# CH32V407VET-USB.net
KiCad netlist of a schematic drawn in Altium Designer
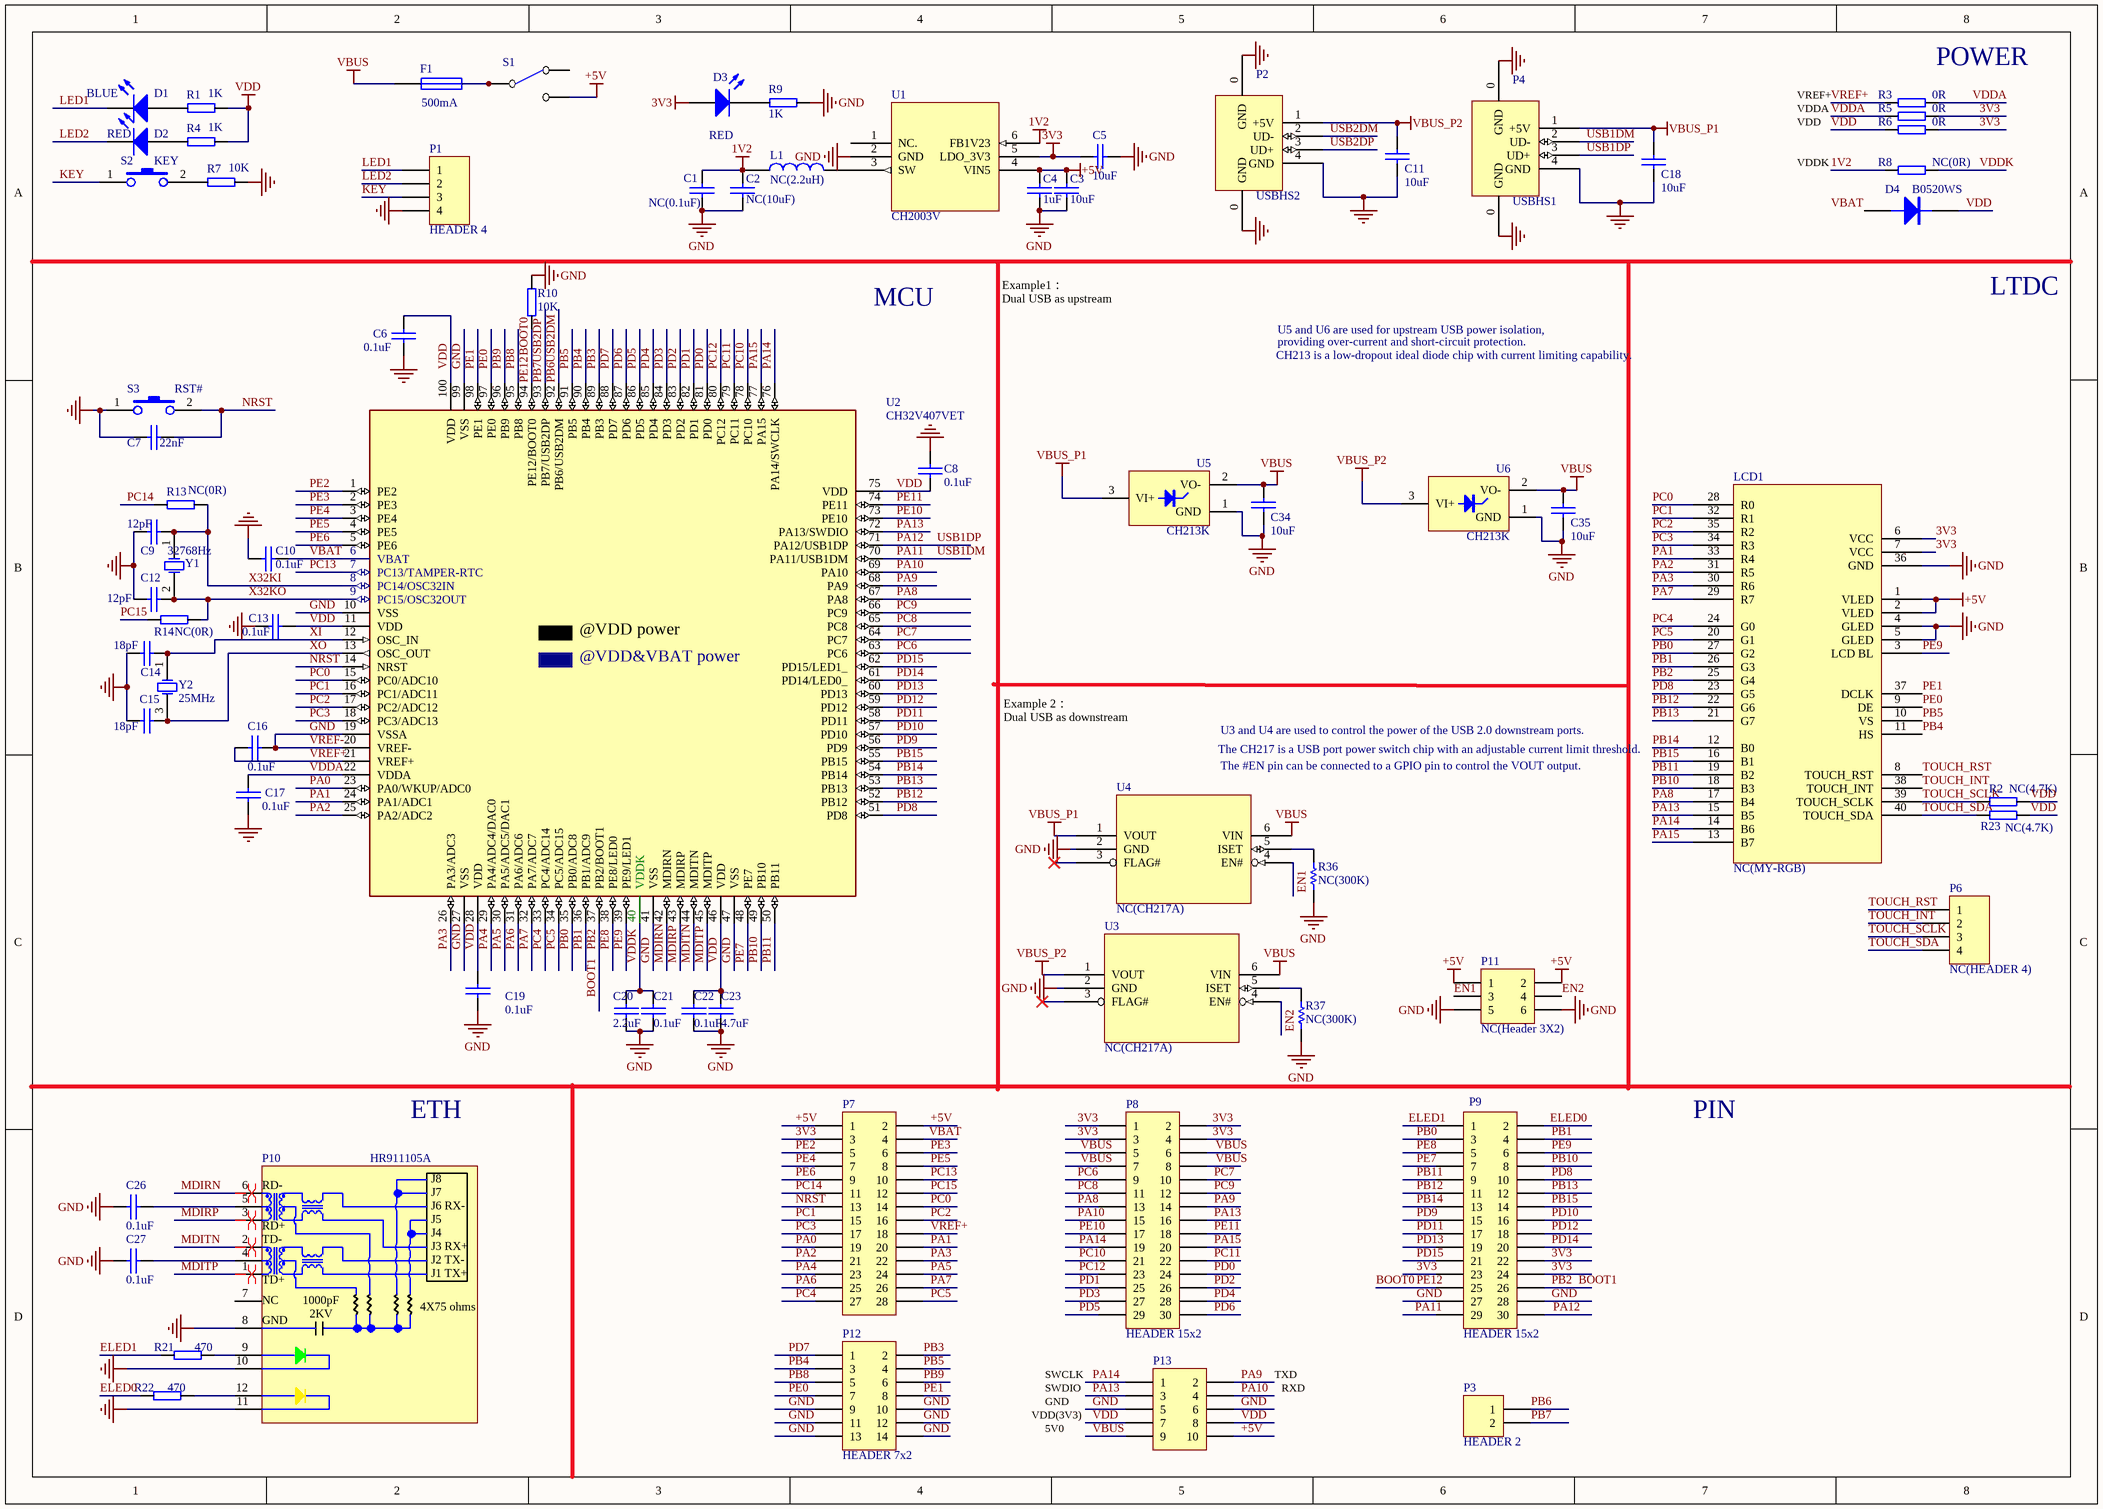
[diagram p0: CH32V407VET-USB.SchDoc]

(export (version "E")
  (design (tool "Eeschema 10.0.6"))
  (components
    (comp (ref "C1")
      (value "NC(0.1uF)")
      (footprint "0402_C")
      (description "Capacitor")
      (libsource (lib "*") (part "CAP"))
    )
    (comp (ref "C2")
      (value "NC(10uF)")
      (footprint "0603_C")
      (description "Capacitor")
      (libsource (lib "") (part "CAP_2"))
    )
    (comp (ref "C3")
      (value "10uF")
      (footprint "0603_C")
      (description "Capacitor")
      (libsource (lib "") (part "CAP_2"))
    )
    (comp (ref "C4")
      (value "1uF")
      (footprint "0402_C")
      (description "Capacitor")
      (libsource (lib "*") (part "CAP"))
    )
    (comp (ref "C5")
      (value "10uF")
      (footprint "0603_C")
      (description "Capacitor")
      (libsource (lib "") (part "CAP_2"))
    )
    (comp (ref "C6")
      (value "0.1uF")
      (footprint "0402_C")
      (description "Capacitor")
      (libsource (lib "") (part "CAP_2"))
    )
    (comp (ref "C7")
      (value "22nF")
      (footprint "0402_C")
      (description "Capacitor")
      (libsource (lib "") (part "CAP_1"))
    )
    (comp (ref "C8")
      (value "0.1uF")
      (footprint "0402_C")
      (description "Capacitor")
      (libsource (lib "") (part "CAP_2"))
    )
    (comp (ref "C9")
      (value "12pF")
      (footprint "0402_C")
      (description "Capacitor")
      (libsource (lib "") (part "CAP_2"))
    )
    (comp (ref "C10")
      (value "0.1uF")
      (footprint "0402_C")
      (description "Capacitor")
      (libsource (lib "") (part "CAP_2"))
    )
    (comp (ref "C11")
      (value "10uF")
      (footprint "0603_C")
      (description "Capacitor")
      (libsource (lib "") (part "CAP_1"))
    )
    (comp (ref "C12")
      (value "12pF")
      (footprint "0402_C")
      (description "Capacitor")
      (libsource (lib "") (part "CAP_2"))
    )
    (comp (ref "C13")
      (value "0.1uF")
      (footprint "0402_C")
      (description "Capacitor")
      (libsource (lib "") (part "CAP_2"))
    )
    (comp (ref "C14")
      (value "18pF")
      (footprint "0402_C")
      (description "Capacitor")
      (libsource (lib "") (part "CAP_2"))
    )
    (comp (ref "C15")
      (value "18pF")
      (footprint "0402_C")
      (description "Capacitor")
      (libsource (lib "") (part "CAP_2"))
    )
    (comp (ref "C16")
      (value "0.1uF")
      (footprint "0402_C")
      (description "Capacitor")
      (libsource (lib "") (part "CAP_2"))
    )
    (comp (ref "C17")
      (value "0.1uF")
      (footprint "0402_C")
      (description "Capacitor")
      (libsource (lib "") (part "CAP_2"))
    )
    (comp (ref "C18")
      (value "10uF")
      (footprint "0603_C")
      (description "Capacitor")
      (libsource (lib "") (part "CAP_1"))
    )
    (comp (ref "C19")
      (value "0.1uF")
      (footprint "0402_C")
      (description "Capacitor")
      (libsource (lib "") (part "CAP_2"))
    )
    (comp (ref "C20")
      (value "2.2uF")
      (footprint "0402_C")
      (description "Capacitor")
      (libsource (lib "") (part "CAP_2"))
    )
    (comp (ref "C21")
      (value "0.1uF")
      (footprint "0402_C")
      (description "Capacitor")
      (libsource (lib "") (part "CAP_2"))
    )
    (comp (ref "C22")
      (value "0.1uF")
      (footprint "0402_C")
      (description "Capacitor")
      (libsource (lib "") (part "CAP_2"))
    )
    (comp (ref "C23")
      (value "4.7uF")
      (footprint "0402_C")
      (description "Capacitor")
      (libsource (lib "") (part "CAP_2"))
    )
    (comp (ref "C26")
      (value "0.1uF")
      (footprint "0402_C")
      (description "Capacitor")
      (libsource (lib "wch_sch_others") (part "CAP"))
    )
    (comp (ref "C27")
      (value "0.1uF")
      (footprint "0402_C")
      (description "Capacitor")
      (libsource (lib "wch_sch_others") (part "CAP"))
    )
    (comp (ref "C34")
      (value "10uF")
      (footprint "0603_C")
      (description "Capacitor")
      (libsource (lib "") (part "CAP_1"))
    )
    (comp (ref "C35")
      (value "10uF")
      (footprint "0603_C")
      (description "Capacitor")
      (libsource (lib "") (part "CAP_1"))
    )
    (comp (ref "D1")
      (value "BLUE")
      (footprint "0603+")
      (description "Typical INFRARED GaAs LED")
      (fields (field (name "PUBLISHER") "Altium Limited"))
      (libsource (lib "*") (part "LED0"))
    )
    (comp (ref "D2")
      (value "RED")
      (footprint "0603+")
      (description "Typical INFRARED GaAs LED")
      (fields (field (name "PUBLISHER") "Altium Limited"))
      (libsource (lib "*") (part "LED0"))
    )
    (comp (ref "D3")
      (value "RED")
      (footprint "0603+")
      (description "Typical INFRARED GaAs LED")
      (fields (field (name "PUBLISHER") "Altium Limited"))
      (libsource (lib "*") (part "LED0"))
    )
    (comp (ref "D4")
      (value "B0520WS")
      (footprint "SOD-323")
      (description "Diode")
      (libsource (lib "*") (part "DIODE"))
    )
    (comp (ref "F1")
      (value "500mA")
      (footprint "0603")
      (description "Fuse")
      (libsource (lib "wch_sch_others") (part "FUSE1"))
    )
    (comp (ref "L1") (value "NC(2.2uH)") (footprint "CD32") (libsource (lib "*") (part "INDUCTOR")))
    (comp (ref "LCD1")
      (value "NC(MY-RGB)")
      (footprint "FPC40P-0.5-FK750M3")
      (libsource (lib "MY-显示") (part "MY-RGB"))
    )
    (comp (ref "P1")
      (value "HEADER 4")
      (footprint "SIP4-2.54mm")
      (description "Header, 4-Pin")
      (libsource (lib "wch_sch_others") (part "HEADER 4"))
    )
    (comp (ref "P2")
      (value "USBHS2")
      (footprint "USBAF")
      (description "USB Port")
      (libsource (lib "*") (part "USB"))
    )
    (comp (ref "P3")
      (value "HEADER 2")
      (footprint "MYPCB:SIP2-2.54mm")
      (description "Header, 2-Pin")
      (libsource (lib "wch_sch_others") (part "HEADER 2"))
    )
    (comp (ref "P4")
      (value "USBHS1")
      (footprint "USBAF")
      (description "USB Port")
      (libsource (lib "*") (part "USB"))
    )
    (comp (ref "P6")
      (value "NC(HEADER 4)")
      (footprint "SIP4-2.54mm")
      (description "Header, 4-Pin")
      (libsource (lib "wch_sch_others") (part "HEADER 4"))
    )
    (comp (ref "P7")
      (value "HEADER 14x2")
      (footprint "MYPCB:IDC28-2.54MM")
      (description "Header, 14-Pin, Dual row")
      (libsource (lib "wch_sch_others") (part "HEADER 14x2"))
    )
    (comp (ref "P8")
      (value "HEADER 15x2")
      (footprint "MYPCB:IDC30-2.54MM")
      (description "Header, 15-Pin, Dual row")
      (libsource (lib "wch_sch_others") (part "HEADER 15x2"))
    )
    (comp (ref "P9")
      (value "HEADER 15x2")
      (footprint "MYPCB:IDC30-2.54MM")
      (description "Header, 15-Pin, Dual row")
      (libsource (lib "wch_sch_others") (part "HEADER 15x2"))
    )
    (comp (ref "P10") (value "HR911105A") (footprint "HR911105A") (libsource (lib "*") (part "HR911105A")))
    (comp (ref "P11")
      (value "NC(Header 3X2)")
      (footprint "HDR2X3")
      (description "Header, 3-Pin, Dual row")
      (fields (field (name "PUBLISHER") "Altium Limited"))
      (libsource (lib "Miscellaneous Connectors") (part "Header 3X2"))
    )
    (comp (ref "P12")
      (value "HEADER 7x2")
      (footprint "MYPCB:IDC14-2.54mm")
      (description "Header, 7-Pin, Dual row")
      (libsource (lib "wch_sch_others") (part "HEADER 7x2"))
    )
    (comp (ref "P13")
      (value "LINK")
      (footprint "IDC10-2.54mm")
      (description "Header, 5-Pin, Dual row, Right Angle")
      (fields (field (name "PUBLISHER") "Altium Limited"))
      (libsource (lib "Miscellaneous Connectors") (part "Header 5X2H"))
    )
    (comp (ref "R1") (value "1K") (footprint "0402") (libsource (lib "wch_sch_others") (part "RES")))
    (comp (ref "R2") (value "NC(4.7K)") (footprint "0402") (libsource (lib "wch_sch_others") (part "RES")))
    (comp (ref "R3") (value "0R") (footprint "0402") (libsource (lib "*") (part "R")))
    (comp (ref "R4") (value "1K") (footprint "0402") (libsource (lib "wch_sch_others") (part "RES")))
    (comp (ref "R5") (value "0R") (footprint "0402") (libsource (lib "*") (part "R")))
    (comp (ref "R6") (value "0R") (footprint "0402") (libsource (lib "*") (part "R")))
    (comp (ref "R7") (value "10K") (footprint "0402") (libsource (lib "wch_sch_others") (part "RES")))
    (comp (ref "R8") (value "NC(0R)") (footprint "0402") (libsource (lib "*") (part "R")))
    (comp (ref "R9") (value "1K") (footprint "0402") (libsource (lib "wch_sch_others") (part "RES")))
    (comp (ref "R10") (value "10K") (footprint "0402") (libsource (lib "wch_sch_others") (part "RES")))
    (comp (ref "R13") (value "NC(0R)") (footprint "0402") (libsource (lib "wch_sch_others") (part "RES")))
    (comp (ref "R14") (value "NC(0R)") (footprint "0402") (libsource (lib "wch_sch_others") (part "RES")))
    (comp (ref "R21") (value "470") (footprint "0402") (libsource (lib "wch_sch_others") (part "RES")))
    (comp (ref "R22") (value "470") (footprint "0402") (libsource (lib "wch_sch_others") (part "RES")))
    (comp (ref "R23") (value "NC(4.7K)") (footprint "0402") (libsource (lib "wch_sch_others") (part "RES")))
    (comp (ref "R36")
      (value "NC(300K)")
      (footprint "0603")
      (description "Resistor")
      (fields (field (name "PUBLISHER") "Altium Limited"))
      (libsource (lib "MYLIB") (part "0603-1"))
    )
    (comp (ref "R37")
      (value "NC(300K)")
      (footprint "0603")
      (description "Resistor")
      (fields (field (name "PUBLISHER") "Altium Limited"))
      (libsource (lib "MYLIB") (part "0603-1"))
    )
    (comp (ref "S1") (value "SW SPDT") (footprint "SW1") (libsource (lib "*") (part "SW SPDT")))
    (comp (ref "S2")
      (value "KEY")
      (footprint "SMD_6.1x3.65x2.5mm-KEY")
      (libsource (lib "wch_sch_others") (part "KEY1"))
    )
    (comp (ref "S3")
      (value "RST#")
      (footprint "SMD_6.1x3.65x2.5mm-KEY")
      (libsource (lib "wch_sch_others") (part "KEY1"))
    )
    (comp (ref "U1")
      (value "CH2003V")
      (footprint "SOT-23-6")
      (description "Step-Down DC-DC Converter, 5V input, 1.23V * 800mA output, with LDO 3.3V * 200mA")
      (libsource (lib "CHXXX") (part "CH2003V"))
    )
    (comp (ref "U2")
      (value "CH32V407VET")
      (footprint "LQFP100")
      (description "RISC-V FPU HD-MCU, 175MHz, USB_480M, 100M Ethernet & Phy, CAN, DVP, ADC, DAC")
      (libsource (lib "CHXXX") (part "CH32V407VET"))
    )
    (comp (ref "U3")
      (value "NC(CH217A)")
      (footprint "SOT-23-6")
      (description "Current-Limited USB Power Distribution Switch")
      (libsource (lib "CHXXX") (part "CH217K"))
    )
    (comp (ref "U4")
      (value "NC(CH217A)")
      (footprint "SOT-23-6")
      (description "Current-Limited USB Power Distribution Switch")
      (libsource (lib "CHXXX") (part "CH217K"))
    )
    (comp (ref "U5")
      (value "CH213K")
      (footprint "SOT-23-3")
      (description "Ideal Diode 5V*1A")
      (libsource (lib "*") (part "CH213K"))
    )
    (comp (ref "U6")
      (value "CH213K")
      (footprint "SOT-23-3")
      (description "Ideal Diode 5V*1A")
      (libsource (lib "*") (part "CH213K"))
    )
    (comp (ref "Y1")
      (value "32768Hz")
      (footprint "FC-135")
      (description "Crystal Oscillator")
      (fields (field (name "PUBLISHER") "Altium Limited"))
      (libsource (lib "") (part "XTAL_1"))
    )
    (comp (ref "Y2")
      (value "25MHz")
      (footprint "XT3225")
      (description "Crystal Oscillator")
      (fields (field (name "PUBLISHER") "Altium Limited"))
      (libsource (lib "*") (part "XTAL"))
    )
  )
  (nets
    (net (code "1") (name "+5V") (class "Default")
      (node (ref "C3") (pin "2") (pinfunction "2_2") (pintype "passive"))
      (node (ref "C4") (pin "2") (pinfunction "2_2") (pintype "passive"))
      (node (ref "LCD1") (pin "1") (pinfunction "VLED_1") (pintype "passive"))
      (node (ref "LCD1") (pin "2") (pinfunction "VLED_2") (pintype "passive"))
      (node (ref "P11") (pin "1") (pinfunction "1_1") (pintype "passive"))
      (node (ref "P11") (pin "2") (pinfunction "2_2") (pintype "passive"))
      (node (ref "P13") (pin "10") (pinfunction "10_10") (pintype "passive"))
      (node (ref "P7") (pin "1") (pinfunction "1_1") (pintype "passive"))
      (node (ref "P7") (pin "2") (pinfunction "2_2") (pintype "passive"))
      (node (ref "S1") (pin "2") (pinfunction "NC_2") (pintype "passive"))
      (node (ref "U1") (pin "4") (pinfunction "VIN5_4") (pintype "power_in"))
    )
    (net (code "3") (name "/BOOT0") (class "Default")
      (node (ref "P9") (pin "25") (pinfunction "25_25") (pintype "passive"))
      (node (ref "R10") (pin "2") (pintype "passive"))
      (node (ref "U2") (pin "94") (pinfunction "PE12/BOOT0_94") (pintype "bidirectional"))
    )
    (net (code "4") (name "/BOOT1") (class "Default")
      (node (ref "LCD1") (pin "25") (pinfunction "G4_25") (pintype "passive"))
      (node (ref "P9") (pin "26") (pinfunction "26_26") (pintype "passive"))
      (node (ref "U2") (pin "37") (pinfunction "PB2/BOOT1_37") (pintype "bidirectional"))
    )
    (net (code "5") (name "/ELED0") (class "Default")
      (node (ref "P9") (pin "2") (pinfunction "2_2") (pintype "passive"))
      (node (ref "R22") (pin "1") (pintype "passive"))
    )
    (net (code "6") (name "/ELED1") (class "Default")
      (node (ref "P9") (pin "1") (pinfunction "1_1") (pintype "passive"))
      (node (ref "R21") (pin "1") (pintype "passive"))
    )
    (net (code "7") (name "/EN1") (class "Default")
      (node (ref "P11") (pin "3") (pinfunction "3_3") (pintype "passive"))
      (node (ref "U4") (pin "4") (pinfunction "EN#_4") (pintype "input"))
    )
    (net (code "8") (name "/EN2") (class "Default")
      (node (ref "P11") (pin "4") (pinfunction "4_4") (pintype "passive"))
      (node (ref "U3") (pin "4") (pinfunction "EN#_4") (pintype "input"))
    )
    (net (code "9") (name "/KEY") (class "Default")
      (node (ref "P1") (pin "3") (pinfunction "3_3") (pintype "passive"))
      (node (ref "S2") (pin "1") (pinfunction "1_1") (pintype "passive"))
    )
    (net (code "10") (name "/LED1") (class "Default")
      (node (ref "D1") (pin "2") (pinfunction "K_2") (pintype "passive"))
      (node (ref "P1") (pin "1") (pinfunction "1_1") (pintype "passive"))
    )
    (net (code "11") (name "/LED2") (class "Default")
      (node (ref "D2") (pin "2") (pinfunction "K_2") (pintype "passive"))
      (node (ref "P1") (pin "2") (pinfunction "2_2") (pintype "passive"))
    )
    (net (code "12") (name "/MDIRN") (class "Default")
      (node (ref "P10") (pin "6") (pintype "passive"))
      (node (ref "U2") (pin "42") (pinfunction "MDIRN_42") (pintype "bidirectional"))
    )
    (net (code "13") (name "/MDIRP") (class "Default")
      (node (ref "P10") (pin "3") (pintype "passive"))
      (node (ref "U2") (pin "43") (pinfunction "MDIRP_43") (pintype "bidirectional"))
    )
    (net (code "14") (name "/MDITN") (class "Default")
      (node (ref "P10") (pin "2") (pintype "passive"))
      (node (ref "U2") (pin "44") (pinfunction "MDITN_44") (pintype "bidirectional"))
    )
    (net (code "15") (name "/MDITP") (class "Default")
      (node (ref "P10") (pin "1") (pintype "passive"))
      (node (ref "U2") (pin "45") (pinfunction "MDITP_45") (pintype "bidirectional"))
    )
    (net (code "16") (name "/NRST") (class "Default")
      (node (ref "C7") (pin "2") (pinfunction "2_2") (pintype "passive"))
      (node (ref "P7") (pin "13") (pinfunction "13_13") (pintype "passive"))
      (node (ref "S3") (pin "2") (pinfunction "2_2") (pintype "passive"))
      (node (ref "U2") (pin "14") (pinfunction "NRST_14") (pintype "input"))
    )
    (net (code "17") (name "/PA0") (class "Default")
      (node (ref "P7") (pin "19") (pinfunction "19_19") (pintype "passive"))
      (node (ref "U2") (pin "23") (pinfunction "PA0/WKUP/ADC0_23") (pintype "bidirectional"))
    )
    (net (code "18") (name "/PA1") (class "Default")
      (node (ref "LCD1") (pin "33") (pinfunction "R4_33") (pintype "passive"))
      (node (ref "P7") (pin "20") (pinfunction "20_20") (pintype "passive"))
      (node (ref "U2") (pin "24") (pinfunction "PA1/ADC1_24") (pintype "bidirectional"))
    )
    (net (code "19") (name "/PA2") (class "Default")
      (node (ref "LCD1") (pin "31") (pinfunction "R5_31") (pintype "passive"))
      (node (ref "P7") (pin "21") (pinfunction "21_21") (pintype "passive"))
      (node (ref "U2") (pin "25") (pinfunction "PA2/ADC2_25") (pintype "bidirectional"))
    )
    (net (code "20") (name "/PA3") (class "Default")
      (node (ref "LCD1") (pin "30") (pinfunction "R6_30") (pintype "passive"))
      (node (ref "P7") (pin "22") (pinfunction "22_22") (pintype "passive"))
      (node (ref "U2") (pin "26") (pinfunction "PA3/ADC3_26") (pintype "bidirectional"))
    )
    (net (code "21") (name "/PA4") (class "Default")
      (node (ref "P7") (pin "23") (pinfunction "23_23") (pintype "passive"))
      (node (ref "U2") (pin "29") (pinfunction "PA4/ADC4/DAC0_29") (pintype "bidirectional"))
    )
    (net (code "22") (name "/PA5") (class "Default")
      (node (ref "P7") (pin "24") (pinfunction "24_24") (pintype "passive"))
      (node (ref "U2") (pin "30") (pinfunction "PA5/ADC5/DAC1_30") (pintype "bidirectional"))
    )
    (net (code "23") (name "/PA6") (class "Default")
      (node (ref "P7") (pin "25") (pinfunction "25_25") (pintype "passive"))
      (node (ref "U2") (pin "31") (pinfunction "PA6/ADC6_31") (pintype "bidirectional"))
    )
    (net (code "24") (name "/PA7") (class "Default")
      (node (ref "LCD1") (pin "29") (pinfunction "R7_29") (pintype "passive"))
      (node (ref "P7") (pin "26") (pinfunction "26_26") (pintype "passive"))
      (node (ref "U2") (pin "32") (pinfunction "PA7/ADC7_32") (pintype "bidirectional"))
    )
    (net (code "25") (name "/PA8") (class "Default")
      (node (ref "LCD1") (pin "17") (pinfunction "B4_17") (pintype "passive"))
      (node (ref "P8") (pin "13") (pinfunction "13_13") (pintype "passive"))
      (node (ref "U2") (pin "67") (pinfunction "PA8_67") (pintype "bidirectional"))
    )
    (net (code "26") (name "/PA9") (class "Default")
      (node (ref "P13") (pin "2") (pinfunction "2_2") (pintype "passive"))
      (node (ref "P8") (pin "14") (pinfunction "14_14") (pintype "passive"))
      (node (ref "U2") (pin "68") (pinfunction "PA9_68") (pintype "bidirectional"))
    )
    (net (code "27") (name "/PA10") (class "Default")
      (node (ref "P13") (pin "4") (pinfunction "4_4") (pintype "passive"))
      (node (ref "P8") (pin "15") (pinfunction "15_15") (pintype "passive"))
      (node (ref "U2") (pin "69") (pinfunction "PA10_69") (pintype "bidirectional"))
    )
    (net (code "28") (name "/PA11") (class "Default")
      (node (ref "P4") (pin "2") (pinfunction "UD-_2") (pintype "bidirectional"))
      (node (ref "P9") (pin "29") (pinfunction "29_29") (pintype "passive"))
      (node (ref "U2") (pin "70") (pinfunction "PA11/USB1DM_70") (pintype "bidirectional"))
    )
    (net (code "29") (name "/PA12") (class "Default")
      (node (ref "P4") (pin "3") (pinfunction "UD+_3") (pintype "bidirectional"))
      (node (ref "P9") (pin "30") (pinfunction "30_30") (pintype "passive"))
      (node (ref "U2") (pin "71") (pinfunction "PA12/USB1DP_71") (pintype "bidirectional"))
    )
    (net (code "30") (name "/PA13") (class "Default")
      (node (ref "LCD1") (pin "15") (pinfunction "B5_15") (pintype "passive"))
      (node (ref "P13") (pin "3") (pinfunction "3_3") (pintype "passive"))
      (node (ref "P8") (pin "16") (pinfunction "16_16") (pintype "passive"))
      (node (ref "U2") (pin "72") (pinfunction "PA13/SWDIO_72") (pintype "bidirectional"))
    )
    (net (code "31") (name "/PA14") (class "Default")
      (node (ref "LCD1") (pin "14") (pinfunction "B6_14") (pintype "passive"))
      (node (ref "P13") (pin "1") (pinfunction "1_1") (pintype "passive"))
      (node (ref "P8") (pin "19") (pinfunction "19_19") (pintype "passive"))
      (node (ref "U2") (pin "76") (pinfunction "PA14/SWCLK_76") (pintype "bidirectional"))
    )
    (net (code "32") (name "/PA15") (class "Default")
      (node (ref "LCD1") (pin "13") (pinfunction "B7_13") (pintype "passive"))
      (node (ref "P8") (pin "20") (pinfunction "20_20") (pintype "passive"))
      (node (ref "U2") (pin "77") (pinfunction "PA15_77") (pintype "bidirectional"))
    )
    (net (code "33") (name "/PB0") (class "Default")
      (node (ref "LCD1") (pin "27") (pinfunction "G2_27") (pintype "passive"))
      (node (ref "P9") (pin "3") (pinfunction "3_3") (pintype "passive"))
      (node (ref "U2") (pin "35") (pinfunction "PB0/ADC8_35") (pintype "bidirectional"))
    )
    (net (code "34") (name "/PB1") (class "Default")
      (node (ref "LCD1") (pin "26") (pinfunction "G3_26") (pintype "passive"))
      (node (ref "P9") (pin "4") (pinfunction "4_4") (pintype "passive"))
      (node (ref "U2") (pin "36") (pinfunction "PB1/ADC9_36") (pintype "bidirectional"))
    )
    (net (code "35") (name "/PB3") (class "Default")
      (node (ref "P12") (pin "2") (pinfunction "2_2") (pintype "passive"))
      (node (ref "U2") (pin "89") (pinfunction "PB3_89") (pintype "bidirectional"))
    )
    (net (code "36") (name "/PB4") (class "Default")
      (node (ref "LCD1") (pin "11") (pinfunction "HS_11") (pintype "passive"))
      (node (ref "P12") (pin "3") (pinfunction "3_3") (pintype "passive"))
      (node (ref "U2") (pin "90") (pinfunction "PB4_90") (pintype "bidirectional"))
    )
    (net (code "37") (name "/PB5") (class "Default")
      (node (ref "LCD1") (pin "10") (pinfunction "VS_10") (pintype "passive"))
      (node (ref "P12") (pin "4") (pinfunction "4_4") (pintype "passive"))
      (node (ref "U2") (pin "91") (pinfunction "PB5_91") (pintype "bidirectional"))
    )
    (net (code "38") (name "/PB6") (class "Default")
      (node (ref "P2") (pin "2") (pinfunction "UD-_2") (pintype "bidirectional"))
      (node (ref "P3") (pin "1") (pinfunction "1_1") (pintype "passive"))
      (node (ref "U2") (pin "92") (pinfunction "PB6/USB2DM_92") (pintype "bidirectional"))
    )
    (net (code "39") (name "/PB7") (class "Default")
      (node (ref "P2") (pin "3") (pinfunction "UD+_3") (pintype "bidirectional"))
      (node (ref "P3") (pin "2") (pinfunction "2_2") (pintype "passive"))
      (node (ref "U2") (pin "93") (pinfunction "PB7/USB2DP_93") (pintype "bidirectional"))
    )
    (net (code "40") (name "/PB8") (class "Default")
      (node (ref "P12") (pin "5") (pinfunction "5_5") (pintype "passive"))
      (node (ref "U2") (pin "95") (pinfunction "PB8_95") (pintype "bidirectional"))
    )
    (net (code "41") (name "/PB9") (class "Default")
      (node (ref "P12") (pin "6") (pinfunction "6_6") (pintype "passive"))
      (node (ref "U2") (pin "96") (pinfunction "PB9_96") (pintype "bidirectional"))
    )
    (net (code "42") (name "/PB10") (class "Default")
      (node (ref "LCD1") (pin "18") (pinfunction "B3_18") (pintype "passive"))
      (node (ref "P9") (pin "8") (pinfunction "8_8") (pintype "passive"))
      (node (ref "U2") (pin "49") (pinfunction "PB10_49") (pintype "bidirectional"))
    )
    (net (code "43") (name "/PB11") (class "Default")
      (node (ref "LCD1") (pin "19") (pinfunction "B2_19") (pintype "passive"))
      (node (ref "P9") (pin "9") (pinfunction "9_9") (pintype "passive"))
      (node (ref "U2") (pin "50") (pinfunction "PB11_50") (pintype "bidirectional"))
    )
    (net (code "44") (name "/PB12") (class "Default")
      (node (ref "LCD1") (pin "22") (pinfunction "G6_22") (pintype "passive"))
      (node (ref "P9") (pin "11") (pinfunction "11_11") (pintype "passive"))
      (node (ref "U2") (pin "52") (pinfunction "PB12_52") (pintype "bidirectional"))
    )
    (net (code "45") (name "/PB13") (class "Default")
      (node (ref "LCD1") (pin "21") (pinfunction "G7_21") (pintype "passive"))
      (node (ref "P9") (pin "12") (pinfunction "12_12") (pintype "passive"))
      (node (ref "U2") (pin "53") (pinfunction "PB13_53") (pintype "bidirectional"))
    )
    (net (code "46") (name "/PB14") (class "Default")
      (node (ref "LCD1") (pin "12") (pinfunction "B0_12") (pintype "passive"))
      (node (ref "P9") (pin "13") (pinfunction "13_13") (pintype "passive"))
      (node (ref "U2") (pin "54") (pinfunction "PB14_54") (pintype "bidirectional"))
    )
    (net (code "47") (name "/PB15") (class "Default")
      (node (ref "LCD1") (pin "16") (pinfunction "B1_16") (pintype "passive"))
      (node (ref "P9") (pin "14") (pinfunction "14_14") (pintype "passive"))
      (node (ref "U2") (pin "55") (pinfunction "PB15_55") (pintype "bidirectional"))
    )
    (net (code "48") (name "/PC0") (class "Default")
      (node (ref "LCD1") (pin "28") (pinfunction "R0_28") (pintype "passive"))
      (node (ref "P7") (pin "14") (pinfunction "14_14") (pintype "passive"))
      (node (ref "U2") (pin "15") (pinfunction "PC0/ADC10_15") (pintype "bidirectional"))
    )
    (net (code "49") (name "/PC1") (class "Default")
      (node (ref "LCD1") (pin "32") (pinfunction "R1_32") (pintype "passive"))
      (node (ref "P7") (pin "15") (pinfunction "15_15") (pintype "passive"))
      (node (ref "U2") (pin "16") (pinfunction "PC1/ADC11_16") (pintype "bidirectional"))
    )
    (net (code "50") (name "/PC2") (class "Default")
      (node (ref "LCD1") (pin "35") (pinfunction "R2_35") (pintype "passive"))
      (node (ref "P7") (pin "16") (pinfunction "16_16") (pintype "passive"))
      (node (ref "U2") (pin "17") (pinfunction "PC2/ADC12_17") (pintype "bidirectional"))
    )
    (net (code "51") (name "/PC3") (class "Default")
      (node (ref "LCD1") (pin "34") (pinfunction "R3_34") (pintype "passive"))
      (node (ref "P7") (pin "17") (pinfunction "17_17") (pintype "passive"))
      (node (ref "U2") (pin "18") (pinfunction "PC3/ADC13_18") (pintype "bidirectional"))
    )
    (net (code "52") (name "/PC4") (class "Default")
      (node (ref "LCD1") (pin "24") (pinfunction "G0_24") (pintype "passive"))
      (node (ref "P7") (pin "27") (pinfunction "27_27") (pintype "passive"))
      (node (ref "U2") (pin "33") (pinfunction "PC4/ADC14_33") (pintype "bidirectional"))
    )
    (net (code "53") (name "/PC5") (class "Default")
      (node (ref "LCD1") (pin "20") (pinfunction "G1_20") (pintype "passive"))
      (node (ref "P7") (pin "28") (pinfunction "28_28") (pintype "passive"))
      (node (ref "U2") (pin "34") (pinfunction "PC5/ADC15_34") (pintype "bidirectional"))
    )
    (net (code "54") (name "/PC6") (class "Default")
      (node (ref "P8") (pin "9") (pinfunction "9_9") (pintype "passive"))
      (node (ref "U2") (pin "63") (pinfunction "PC6_63") (pintype "bidirectional"))
    )
    (net (code "55") (name "/PC7") (class "Default")
      (node (ref "P8") (pin "10") (pinfunction "10_10") (pintype "passive"))
      (node (ref "U2") (pin "64") (pinfunction "PC7_64") (pintype "bidirectional"))
    )
    (net (code "56") (name "/PC8") (class "Default")
      (node (ref "P8") (pin "11") (pinfunction "11_11") (pintype "passive"))
      (node (ref "U2") (pin "65") (pinfunction "PC8_65") (pintype "bidirectional"))
    )
    (net (code "57") (name "/PC9") (class "Default")
      (node (ref "P8") (pin "12") (pinfunction "12_12") (pintype "passive"))
      (node (ref "U2") (pin "66") (pinfunction "PC9_66") (pintype "bidirectional"))
    )
    (net (code "58") (name "/PC10") (class "Default")
      (node (ref "P8") (pin "21") (pinfunction "21_21") (pintype "passive"))
      (node (ref "U2") (pin "78") (pinfunction "PC10_78") (pintype "bidirectional"))
    )
    (net (code "59") (name "/PC11") (class "Default")
      (node (ref "P8") (pin "22") (pinfunction "22_22") (pintype "passive"))
      (node (ref "U2") (pin "79") (pinfunction "PC11_79") (pintype "bidirectional"))
    )
    (net (code "60") (name "/PC12") (class "Default")
      (node (ref "P8") (pin "23") (pinfunction "23_23") (pintype "passive"))
      (node (ref "U2") (pin "80") (pinfunction "PC12_80") (pintype "bidirectional"))
    )
    (net (code "61") (name "/PC13") (class "Default")
      (node (ref "P7") (pin "10") (pinfunction "10_10") (pintype "passive"))
      (node (ref "U2") (pin "7") (pinfunction "PC13/TAMPER-RTC_7") (pintype "bidirectional"))
    )
    (net (code "62") (name "/PC14") (class "Default")
      (node (ref "P7") (pin "11") (pinfunction "11_11") (pintype "passive"))
      (node (ref "R13") (pin "1") (pintype "passive"))
    )
    (net (code "63") (name "/PC15") (class "Default")
      (node (ref "P7") (pin "12") (pinfunction "12_12") (pintype "passive"))
      (node (ref "R14") (pin "1") (pintype "passive"))
    )
    (net (code "64") (name "/PD0") (class "Default")
      (node (ref "P8") (pin "24") (pinfunction "24_24") (pintype "passive"))
      (node (ref "U2") (pin "81") (pinfunction "PD0_81") (pintype "bidirectional"))
    )
    (net (code "65") (name "/PD1") (class "Default")
      (node (ref "P8") (pin "25") (pinfunction "25_25") (pintype "passive"))
      (node (ref "U2") (pin "82") (pinfunction "PD1_82") (pintype "bidirectional"))
    )
    (net (code "66") (name "/PD2") (class "Default")
      (node (ref "P8") (pin "26") (pinfunction "26_26") (pintype "passive"))
      (node (ref "U2") (pin "83") (pinfunction "PD2_83") (pintype "bidirectional"))
    )
    (net (code "67") (name "/PD3") (class "Default")
      (node (ref "P8") (pin "27") (pinfunction "27_27") (pintype "passive"))
      (node (ref "U2") (pin "84") (pinfunction "PD3_84") (pintype "bidirectional"))
    )
    (net (code "68") (name "/PD4") (class "Default")
      (node (ref "P8") (pin "28") (pinfunction "28_28") (pintype "passive"))
      (node (ref "U2") (pin "85") (pinfunction "PD4_85") (pintype "bidirectional"))
    )
    (net (code "69") (name "/PD5") (class "Default")
      (node (ref "P8") (pin "29") (pinfunction "29_29") (pintype "passive"))
      (node (ref "U2") (pin "86") (pinfunction "PD5_86") (pintype "bidirectional"))
    )
    (net (code "70") (name "/PD6") (class "Default")
      (node (ref "P8") (pin "30") (pinfunction "30_30") (pintype "passive"))
      (node (ref "U2") (pin "87") (pinfunction "PD6_87") (pintype "bidirectional"))
    )
    (net (code "71") (name "/PD7") (class "Default")
      (node (ref "P12") (pin "1") (pinfunction "1_1") (pintype "passive"))
      (node (ref "U2") (pin "88") (pinfunction "PD7_88") (pintype "bidirectional"))
    )
    (net (code "72") (name "/PD8") (class "Default")
      (node (ref "LCD1") (pin "23") (pinfunction "G5_23") (pintype "passive"))
      (node (ref "P9") (pin "10") (pinfunction "10_10") (pintype "passive"))
      (node (ref "U2") (pin "51") (pinfunction "PD8_51") (pintype "bidirectional"))
    )
    (net (code "73") (name "/PD9") (class "Default")
      (node (ref "P9") (pin "15") (pinfunction "15_15") (pintype "passive"))
      (node (ref "U2") (pin "56") (pinfunction "PD9_56") (pintype "bidirectional"))
    )
    (net (code "74") (name "/PD10") (class "Default")
      (node (ref "P9") (pin "16") (pinfunction "16_16") (pintype "passive"))
      (node (ref "U2") (pin "57") (pinfunction "PD10_57") (pintype "bidirectional"))
    )
    (net (code "75") (name "/PD11") (class "Default")
      (node (ref "P9") (pin "17") (pinfunction "17_17") (pintype "passive"))
      (node (ref "U2") (pin "58") (pinfunction "PD11_58") (pintype "bidirectional"))
    )
    (net (code "76") (name "/PD12") (class "Default")
      (node (ref "P9") (pin "18") (pinfunction "18_18") (pintype "passive"))
      (node (ref "U2") (pin "59") (pinfunction "PD12_59") (pintype "bidirectional"))
    )
    (net (code "77") (name "/PD13") (class "Default")
      (node (ref "P9") (pin "19") (pinfunction "19_19") (pintype "passive"))
      (node (ref "U2") (pin "60") (pinfunction "PD13_60") (pintype "bidirectional"))
    )
    (net (code "78") (name "/PD14") (class "Default")
      (node (ref "P9") (pin "20") (pinfunction "20_20") (pintype "passive"))
      (node (ref "U2") (pin "61") (pinfunction "PD14/LED0__61") (pintype "bidirectional"))
    )
    (net (code "79") (name "/PD15") (class "Default")
      (node (ref "P9") (pin "21") (pinfunction "21_21") (pintype "passive"))
      (node (ref "U2") (pin "62") (pinfunction "PD15/LED1__62") (pintype "bidirectional"))
    )
    (net (code "80") (name "/PE0") (class "Default")
      (node (ref "LCD1") (pin "9") (pinfunction "DE_9") (pintype "passive"))
      (node (ref "P12") (pin "7") (pinfunction "7_7") (pintype "passive"))
      (node (ref "U2") (pin "97") (pinfunction "PE0_97") (pintype "bidirectional"))
    )
    (net (code "81") (name "/PE1") (class "Default")
      (node (ref "LCD1") (pin "37") (pinfunction "DCLK_37") (pintype "passive"))
      (node (ref "P12") (pin "8") (pinfunction "8_8") (pintype "passive"))
      (node (ref "U2") (pin "98") (pinfunction "PE1_98") (pintype "bidirectional"))
    )
    (net (code "82") (name "/PE2") (class "Default")
      (node (ref "P7") (pin "5") (pinfunction "5_5") (pintype "passive"))
      (node (ref "U2") (pin "1") (pinfunction "PE2_1") (pintype "bidirectional"))
    )
    (net (code "83") (name "/PE3") (class "Default")
      (node (ref "P7") (pin "6") (pinfunction "6_6") (pintype "passive"))
      (node (ref "U2") (pin "2") (pinfunction "PE3_2") (pintype "bidirectional"))
    )
    (net (code "84") (name "/PE4") (class "Default")
      (node (ref "P7") (pin "7") (pinfunction "7_7") (pintype "passive"))
      (node (ref "U2") (pin "3") (pinfunction "PE4_3") (pintype "bidirectional"))
    )
    (net (code "85") (name "/PE5") (class "Default")
      (node (ref "P7") (pin "8") (pinfunction "8_8") (pintype "passive"))
      (node (ref "U2") (pin "4") (pinfunction "PE5_4") (pintype "bidirectional"))
    )
    (net (code "86") (name "/PE6") (class "Default")
      (node (ref "P7") (pin "9") (pinfunction "9_9") (pintype "passive"))
      (node (ref "U2") (pin "5") (pinfunction "PE6_5") (pintype "bidirectional"))
    )
    (net (code "87") (name "/PE7") (class "Default")
      (node (ref "P9") (pin "7") (pinfunction "7_7") (pintype "passive"))
      (node (ref "U2") (pin "48") (pinfunction "PE7_48") (pintype "bidirectional"))
    )
    (net (code "88") (name "/PE8") (class "Default")
      (node (ref "P9") (pin "5") (pinfunction "5_5") (pintype "passive"))
      (node (ref "U2") (pin "38") (pinfunction "PE8/LED0_38") (pintype "bidirectional"))
    )
    (net (code "89") (name "/PE9") (class "Default")
      (node (ref "LCD1") (pin "3") (pinfunction "LCD_BL_3") (pintype "passive"))
      (node (ref "P9") (pin "6") (pinfunction "6_6") (pintype "passive"))
      (node (ref "U2") (pin "39") (pinfunction "PE9/LED1_39") (pintype "bidirectional"))
    )
    (net (code "90") (name "/PE10") (class "Default")
      (node (ref "P8") (pin "17") (pinfunction "17_17") (pintype "passive"))
      (node (ref "U2") (pin "73") (pinfunction "PE10_73") (pintype "bidirectional"))
    )
    (net (code "91") (name "/PE11") (class "Default")
      (node (ref "P8") (pin "18") (pinfunction "18_18") (pintype "passive"))
      (node (ref "U2") (pin "74") (pinfunction "PE11_74") (pintype "bidirectional"))
    )
    (net (code "92") (name "/TOUCH_INT") (class "Default")
      (node (ref "LCD1") (pin "38") (pinfunction "TOUCH_INT_38") (pintype "passive"))
      (node (ref "P6") (pin "2") (pinfunction "2_2") (pintype "passive"))
    )
    (net (code "93") (name "/TOUCH_RST") (class "Default")
      (node (ref "LCD1") (pin "8") (pinfunction "TOUCH_RST_8") (pintype "passive"))
      (node (ref "P6") (pin "1") (pinfunction "1_1") (pintype "passive"))
    )
    (net (code "94") (name "/TOUCH_SCLK") (class "Default")
      (node (ref "LCD1") (pin "39") (pinfunction "TOUCH_SCLK_39") (pintype "passive"))
      (node (ref "P6") (pin "3") (pinfunction "3_3") (pintype "passive"))
      (node (ref "R2") (pin "2") (pintype "passive"))
    )
    (net (code "95") (name "/TOUCH_SDA") (class "Default")
      (node (ref "LCD1") (pin "40") (pinfunction "TOUCH_SDA_40") (pintype "passive"))
      (node (ref "P6") (pin "4") (pinfunction "4_4") (pintype "passive"))
      (node (ref "R23") (pin "2") (pintype "passive"))
    )
    (net (code "96") (name "/VBAT") (class "Default")
      (node (ref "C10") (pin "2") (pinfunction "2_2") (pintype "passive"))
      (node (ref "P7") (pin "4") (pinfunction "4_4") (pintype "passive"))
      (node (ref "U2") (pin "6") (pinfunction "VBAT_6") (pintype "power_in"))
    )
    (net (code "97") (name "/VDDA") (class "Default")
      (node (ref "C17") (pin "1") (pinfunction "1_1") (pintype "passive"))
      (node (ref "R3") (pin "1") (pinfunction "1_1") (pintype "passive"))
      (node (ref "R5") (pin "2") (pinfunction "2_2") (pintype "passive"))
      (node (ref "U2") (pin "22") (pinfunction "VDDA_22") (pintype "power_in"))
    )
    (net (code "98") (name "/VDDK") (class "Default")
      (node (ref "C20") (pin "2") (pinfunction "2_2") (pintype "passive"))
      (node (ref "C21") (pin "2") (pinfunction "2_2") (pintype "passive"))
      (node (ref "R8") (pin "1") (pinfunction "1_1") (pintype "passive"))
      (node (ref "U2") (pin "40") (pinfunction "VDDK_40") (pintype "power_in"))
    )
    (net (code "99") (name "/VREF+") (class "Default")
      (node (ref "C16") (pin "1") (pinfunction "1_1") (pintype "passive"))
      (node (ref "P7") (pin "18") (pinfunction "18_18") (pintype "passive"))
      (node (ref "R3") (pin "2") (pinfunction "2_2") (pintype "passive"))
      (node (ref "U2") (pin "21") (pinfunction "VREF+_21") (pintype "power_in"))
    )
    (net (code "100") (name "/X32KI") (class "Default")
      (node (ref "C9") (pin "2") (pinfunction "2_2") (pintype "passive"))
      (node (ref "R13") (pin "2") (pintype "passive"))
      (node (ref "U2") (pin "8") (pinfunction "PC14/OSC32IN_8") (pintype "bidirectional"))
      (node (ref "Y1") (pin "1") (pinfunction "OSC1_1") (pintype "passive"))
    )
    (net (code "101") (name "/X32KO") (class "Default")
      (node (ref "C12") (pin "2") (pinfunction "2_2") (pintype "passive"))
      (node (ref "R14") (pin "2") (pintype "passive"))
      (node (ref "U2") (pin "9") (pinfunction "PC15/OSC32OUT_9") (pintype "bidirectional"))
      (node (ref "Y1") (pin "2") (pinfunction "OSC2_2") (pintype "passive"))
    )
    (net (code "102") (name "/XI") (class "Default")
      (node (ref "C14") (pin "2") (pinfunction "2_2") (pintype "passive"))
      (node (ref "U2") (pin "12") (pinfunction "OSC_IN_12") (pintype "input"))
      (node (ref "Y2") (pin "1") (pinfunction "OSC1_1") (pintype "passive"))
    )
    (net (code "103") (name "/XO") (class "Default")
      (node (ref "C15") (pin "2") (pinfunction "2_2") (pintype "passive"))
      (node (ref "U2") (pin "13") (pinfunction "OSC_OUT_13") (pintype "output"))
      (node (ref "Y2") (pin "3") (pinfunction "OSC2_3") (pintype "passive"))
    )
    (net (code "104") (name "1V2") (class "Default")
      (node (ref "C1") (pin "2") (pinfunction "2_2") (pintype "passive"))
      (node (ref "C2") (pin "2") (pinfunction "2_2") (pintype "passive"))
      (node (ref "L1") (pin "2") (pinfunction "2_2") (pintype "passive"))
      (node (ref "R8") (pin "2") (pinfunction "2_2") (pintype "passive"))
      (node (ref "U1") (pin "6") (pinfunction "FB1V23_6") (pintype "input"))
    )
    (net (code "105") (name "3V3") (class "Default")
      (node (ref "C5") (pin "2") (pinfunction "2_2") (pintype "passive"))
      (node (ref "D3") (pin "1") (pinfunction "A_1") (pintype "passive"))
      (node (ref "LCD1") (pin "6") (pinfunction "VCC_6") (pintype "passive"))
      (node (ref "LCD1") (pin "7") (pinfunction "VCC_7") (pintype "passive"))
      (node (ref "P7") (pin "3") (pinfunction "3_3") (pintype "passive"))
      (node (ref "P8") (pin "1") (pinfunction "1_1") (pintype "passive"))
      (node (ref "P8") (pin "2") (pinfunction "2_2") (pintype "passive"))
      (node (ref "P8") (pin "3") (pinfunction "3_3") (pintype "passive"))
      (node (ref "P8") (pin "4") (pinfunction "4_4") (pintype "passive"))
      (node (ref "P9") (pin "22") (pinfunction "22_22") (pintype "passive"))
      (node (ref "P9") (pin "23") (pinfunction "23_23") (pintype "passive"))
      (node (ref "P9") (pin "24") (pinfunction "24_24") (pintype "passive"))
      (node (ref "R5") (pin "1") (pinfunction "1_1") (pintype "passive"))
      (node (ref "R6") (pin "1") (pinfunction "1_1") (pintype "passive"))
      (node (ref "U1") (pin "5") (pinfunction "LDO_3V3_5") (pintype "power_in"))
    )
    (net (code "106") (name "GND") (class "Default")
      (node (ref "C1") (pin "1") (pinfunction "1_1") (pintype "passive"))
      (node (ref "C10") (pin "1") (pinfunction "1_1") (pintype "passive"))
      (node (ref "C11") (pin "2") (pinfunction "2_2") (pintype "passive"))
      (node (ref "C12") (pin "1") (pinfunction "1_1") (pintype "passive"))
      (node (ref "C13") (pin "2") (pinfunction "2_2") (pintype "passive"))
      (node (ref "C14") (pin "1") (pinfunction "1_1") (pintype "passive"))
      (node (ref "C15") (pin "1") (pinfunction "1_1") (pintype "passive"))
      (node (ref "C16") (pin "2") (pinfunction "2_2") (pintype "passive"))
      (node (ref "C17") (pin "2") (pinfunction "2_2") (pintype "passive"))
      (node (ref "C18") (pin "2") (pinfunction "2_2") (pintype "passive"))
      (node (ref "C19") (pin "1") (pinfunction "1_1") (pintype "passive"))
      (node (ref "C2") (pin "1") (pinfunction "1_1") (pintype "passive"))
      (node (ref "C20") (pin "1") (pinfunction "1_1") (pintype "passive"))
      (node (ref "C21") (pin "1") (pinfunction "1_1") (pintype "passive"))
      (node (ref "C22") (pin "1") (pinfunction "1_1") (pintype "passive"))
      (node (ref "C23") (pin "1") (pinfunction "1_1") (pintype "passive"))
      (node (ref "C26") (pin "1") (pinfunction "1_1") (pintype "passive"))
      (node (ref "C27") (pin "1") (pinfunction "1_1") (pintype "passive"))
      (node (ref "C3") (pin "1") (pinfunction "1_1") (pintype "passive"))
      (node (ref "C34") (pin "2") (pinfunction "2_2") (pintype "passive"))
      (node (ref "C35") (pin "2") (pinfunction "2_2") (pintype "passive"))
      (node (ref "C4") (pin "1") (pinfunction "1_1") (pintype "passive"))
      (node (ref "C5") (pin "1") (pinfunction "1_1") (pintype "passive"))
      (node (ref "C6") (pin "1") (pinfunction "1_1") (pintype "passive"))
      (node (ref "C7") (pin "1") (pinfunction "1_1") (pintype "passive"))
      (node (ref "C8") (pin "2") (pinfunction "2_2") (pintype "passive"))
      (node (ref "C9") (pin "1") (pinfunction "1_1") (pintype "passive"))
      (node (ref "LCD1") (pin "36") (pinfunction "GND_36") (pintype "passive"))
      (node (ref "LCD1") (pin "4") (pinfunction "GLED_4") (pintype "passive"))
      (node (ref "LCD1") (pin "5") (pinfunction "GLED_5") (pintype "passive"))
      (node (ref "P1") (pin "4") (pinfunction "4_4") (pintype "passive"))
      (node (ref "P10") (pin "10") (pintype "passive"))
      (node (ref "P10") (pin "11") (pintype "passive"))
      (node (ref "P10") (pin "8") (pintype "passive"))
      (node (ref "P11") (pin "5") (pinfunction "5_5") (pintype "passive"))
      (node (ref "P11") (pin "6") (pinfunction "6_6") (pintype "passive"))
      (node (ref "P12") (pin "10") (pinfunction "10_10") (pintype "passive"))
      (node (ref "P12") (pin "11") (pinfunction "11_11") (pintype "passive"))
      (node (ref "P12") (pin "12") (pinfunction "12_12") (pintype "passive"))
      (node (ref "P12") (pin "13") (pinfunction "13_13") (pintype "passive"))
      (node (ref "P12") (pin "14") (pinfunction "14_14") (pintype "passive"))
      (node (ref "P12") (pin "9") (pinfunction "9_9") (pintype "passive"))
      (node (ref "P13") (pin "5") (pinfunction "5_5") (pintype "passive"))
      (node (ref "P13") (pin "6") (pinfunction "6_6") (pintype "passive"))
      (node (ref "P2") (pin "0") (pinfunction "GND_0") (pintype "power_in"))
      (node (ref "P2") (pin "4") (pinfunction "GND_4") (pintype "power_in"))
      (node (ref "P4") (pin "0") (pinfunction "GND_0") (pintype "power_in"))
      (node (ref "P4") (pin "4") (pinfunction "GND_4") (pintype "power_in"))
      (node (ref "P9") (pin "27") (pinfunction "27_27") (pintype "passive"))
      (node (ref "P9") (pin "28") (pinfunction "28_28") (pintype "passive"))
      (node (ref "R10") (pin "1") (pintype "passive"))
      (node (ref "R36") (pin "2") (pinfunction "2_2") (pintype "passive"))
      (node (ref "R37") (pin "2") (pinfunction "2_2") (pintype "passive"))
      (node (ref "R7") (pin "1") (pintype "passive"))
      (node (ref "R9") (pin "2") (pintype "passive"))
      (node (ref "S3") (pin "1") (pinfunction "1_1") (pintype "passive"))
      (node (ref "U1") (pin "2") (pinfunction "GND_2") (pintype "power_in"))
      (node (ref "U2") (pin "10") (pinfunction "VSS_10") (pintype "power_in"))
      (node (ref "U2") (pin "19") (pinfunction "VSSA_19") (pintype "power_in"))
      (node (ref "U2") (pin "20") (pinfunction "VREF-_20") (pintype "power_in"))
      (node (ref "U2") (pin "27") (pinfunction "VSS_27") (pintype "power_in"))
      (node (ref "U2") (pin "41") (pinfunction "VSS_41") (pintype "power_in"))
      (node (ref "U2") (pin "47") (pinfunction "VSS_47") (pintype "power_in"))
      (node (ref "U2") (pin "99") (pinfunction "VSS_99") (pintype "power_in"))
      (node (ref "U3") (pin "2") (pinfunction "GND_2") (pintype "power_in"))
      (node (ref "U4") (pin "2") (pinfunction "GND_2") (pintype "power_in"))
      (node (ref "U5") (pin "1") (pinfunction "GND_1") (pintype "power_in"))
      (node (ref "U6") (pin "1") (pinfunction "GND_1") (pintype "power_in"))
    )
    (net (code "107") (name "Net-(C26-Pad2)") (class "Default")
      (node (ref "C26") (pin "2") (pinfunction "2_2") (pintype "passive"))
      (node (ref "P10") (pin "5") (pintype "passive"))
    )
    (net (code "108") (name "Net-(C27-Pad2)") (class "Default")
      (node (ref "C27") (pin "2") (pinfunction "2_2") (pintype "passive"))
      (node (ref "P10") (pin "4") (pintype "passive"))
    )
    (net (code "109") (name "Net-(D1-A)") (class "Default")
      (node (ref "D1") (pin "1") (pinfunction "A_1") (pintype "passive"))
      (node (ref "R1") (pin "2") (pintype "passive"))
    )
    (net (code "110") (name "Net-(D2-A)") (class "Default")
      (node (ref "D2") (pin "1") (pinfunction "A_1") (pintype "passive"))
      (node (ref "R4") (pin "2") (pintype "passive"))
    )
    (net (code "111") (name "Net-(D3-K)") (class "Default")
      (node (ref "D3") (pin "2") (pinfunction "K_2") (pintype "passive"))
      (node (ref "R9") (pin "1") (pintype "passive"))
    )
    (net (code "112") (name "Net-(P10-Pad9)") (class "Default")
      (node (ref "P10") (pin "9") (pintype "passive"))
      (node (ref "R21") (pin "2") (pintype "passive"))
    )
    (net (code "113") (name "Net-(P10-Pad12)") (class "Default")
      (node (ref "P10") (pin "12") (pintype "passive"))
      (node (ref "R22") (pin "2") (pintype "passive"))
    )
    (net (code "114") (name "Net-(R7-Pad2)") (class "Default")
      (node (ref "R7") (pin "2") (pintype "passive"))
      (node (ref "S2") (pin "2") (pinfunction "2_2") (pintype "passive"))
    )
    (net (code "115") (name "Net-(S1-COMMON)") (class "Default")
      (node (ref "F1") (pin "2") (pinfunction "2_2") (pintype "passive"))
      (node (ref "S1") (pin "1") (pinfunction "COMMON_1") (pintype "passive"))
    )
    (net (code "116") (name "Net-(U1-SW)") (class "Default")
      (node (ref "L1") (pin "1") (pinfunction "1_1") (pintype "passive"))
      (node (ref "U1") (pin "3") (pinfunction "SW_3") (pintype "output"))
    )
    (net (code "117") (name "Net-(U3-ISET)") (class "Default")
      (node (ref "R37") (pin "1") (pinfunction "1_1") (pintype "passive"))
      (node (ref "U3") (pin "5") (pinfunction "ISET_5") (pintype "bidirectional"))
    )
    (net (code "118") (name "Net-(U4-ISET)") (class "Default")
      (node (ref "R36") (pin "1") (pinfunction "1_1") (pintype "passive"))
      (node (ref "U4") (pin "5") (pinfunction "ISET_5") (pintype "bidirectional"))
    )
    (net (code "119") (name "VBUS") (class "Default")
      (node (ref "C34") (pin "1") (pinfunction "1_1") (pintype "passive"))
      (node (ref "C35") (pin "1") (pinfunction "1_1") (pintype "passive"))
      (node (ref "F1") (pin "1") (pinfunction "1_1") (pintype "passive"))
      (node (ref "P13") (pin "9") (pinfunction "9_9") (pintype "passive"))
      (node (ref "P8") (pin "5") (pinfunction "5_5") (pintype "passive"))
      (node (ref "P8") (pin "6") (pinfunction "6_6") (pintype "passive"))
      (node (ref "P8") (pin "7") (pinfunction "7_7") (pintype "passive"))
      (node (ref "P8") (pin "8") (pinfunction "8_8") (pintype "passive"))
      (node (ref "U3") (pin "6") (pinfunction "VIN_6") (pintype "power_in"))
      (node (ref "U4") (pin "6") (pinfunction "VIN_6") (pintype "power_in"))
      (node (ref "U5") (pin "2") (pinfunction "VO-_2") (pintype "power_in"))
      (node (ref "U6") (pin "2") (pinfunction "VO-_2") (pintype "power_in"))
    )
    (net (code "120") (name "VBUS_P1") (class "Default")
      (node (ref "C18") (pin "1") (pinfunction "1_1") (pintype "passive"))
      (node (ref "P4") (pin "1") (pinfunction "+5V_1") (pintype "power_in"))
      (node (ref "U4") (pin "1") (pinfunction "VOUT_1") (pintype "power_in"))
      (node (ref "U5") (pin "3") (pinfunction "VI+_3") (pintype "power_in"))
    )
    (net (code "121") (name "VBUS_P2") (class "Default")
      (node (ref "C11") (pin "1") (pinfunction "1_1") (pintype "passive"))
      (node (ref "P2") (pin "1") (pinfunction "+5V_1") (pintype "power_in"))
      (node (ref "U3") (pin "1") (pinfunction "VOUT_1") (pintype "power_in"))
      (node (ref "U6") (pin "3") (pinfunction "VI+_3") (pintype "power_in"))
    )
    (net (code "122") (name "VDD") (class "Default")
      (node (ref "C13") (pin "1") (pinfunction "1_1") (pintype "passive"))
      (node (ref "C19") (pin "2") (pinfunction "2_2") (pintype "passive"))
      (node (ref "C22") (pin "2") (pinfunction "2_2") (pintype "passive"))
      (node (ref "C23") (pin "2") (pinfunction "2_2") (pintype "passive"))
      (node (ref "C6") (pin "2") (pinfunction "2_2") (pintype "passive"))
      (node (ref "C8") (pin "1") (pinfunction "1_1") (pintype "passive"))
      (node (ref "D4") (pin "2") (pinfunction "K_2") (pintype "passive"))
      (node (ref "P13") (pin "7") (pinfunction "7_7") (pintype "passive"))
      (node (ref "P13") (pin "8") (pinfunction "8_8") (pintype "passive"))
      (node (ref "R1") (pin "1") (pintype "passive"))
      (node (ref "R2") (pin "1") (pintype "passive"))
      (node (ref "R23") (pin "1") (pintype "passive"))
      (node (ref "R4") (pin "1") (pintype "passive"))
      (node (ref "R6") (pin "2") (pinfunction "2_2") (pintype "passive"))
      (node (ref "U2") (pin "100") (pinfunction "VDD_100") (pintype "power_in"))
      (node (ref "U2") (pin "11") (pinfunction "VDD_11") (pintype "power_in"))
      (node (ref "U2") (pin "28") (pinfunction "VDD_28") (pintype "power_in"))
      (node (ref "U2") (pin "46") (pinfunction "VDD_46") (pintype "power_in"))
      (node (ref "U2") (pin "75") (pinfunction "VDD_75") (pintype "power_in"))
    )
    (net (code "123") (name "unconnected-(D4-A-Pad1)") (class "Default")
      (node (ref "D4") (pin "1") (pinfunction "A_1") (pintype "passive"))
    )
    (net (code "124") (name "unconnected-(P10-Pad7)") (class "Default")
      (node (ref "P10") (pin "7") (pintype "passive"))
    )
    (net (code "125") (name "unconnected-(S1-NO-Pad3)") (class "Default")
      (node (ref "S1") (pin "3") (pinfunction "NO_3") (pintype "passive"))
    )
    (net (code "126") (name "unconnected-(U1-NC.-Pad1)") (class "Default")
      (node (ref "U1") (pin "1") (pinfunction "NC._1") (pintype "passive"))
    )
    (net (code "127") (name "unconnected-(U3-FLAG#-Pad3)") (class "Default")
      (node (ref "U3") (pin "3") (pinfunction "FLAG#_3") (pintype "open_collector+no_connect"))
    )
    (net (code "128") (name "unconnected-(U4-FLAG#-Pad3)") (class "Default")
      (node (ref "U4") (pin "3") (pinfunction "FLAG#_3") (pintype "open_collector+no_connect"))
    )
  )
)
